# c64-magic-desk-cartridge-smd-256kb.net
KiCad netlist of a schematic drawn in EAGLE
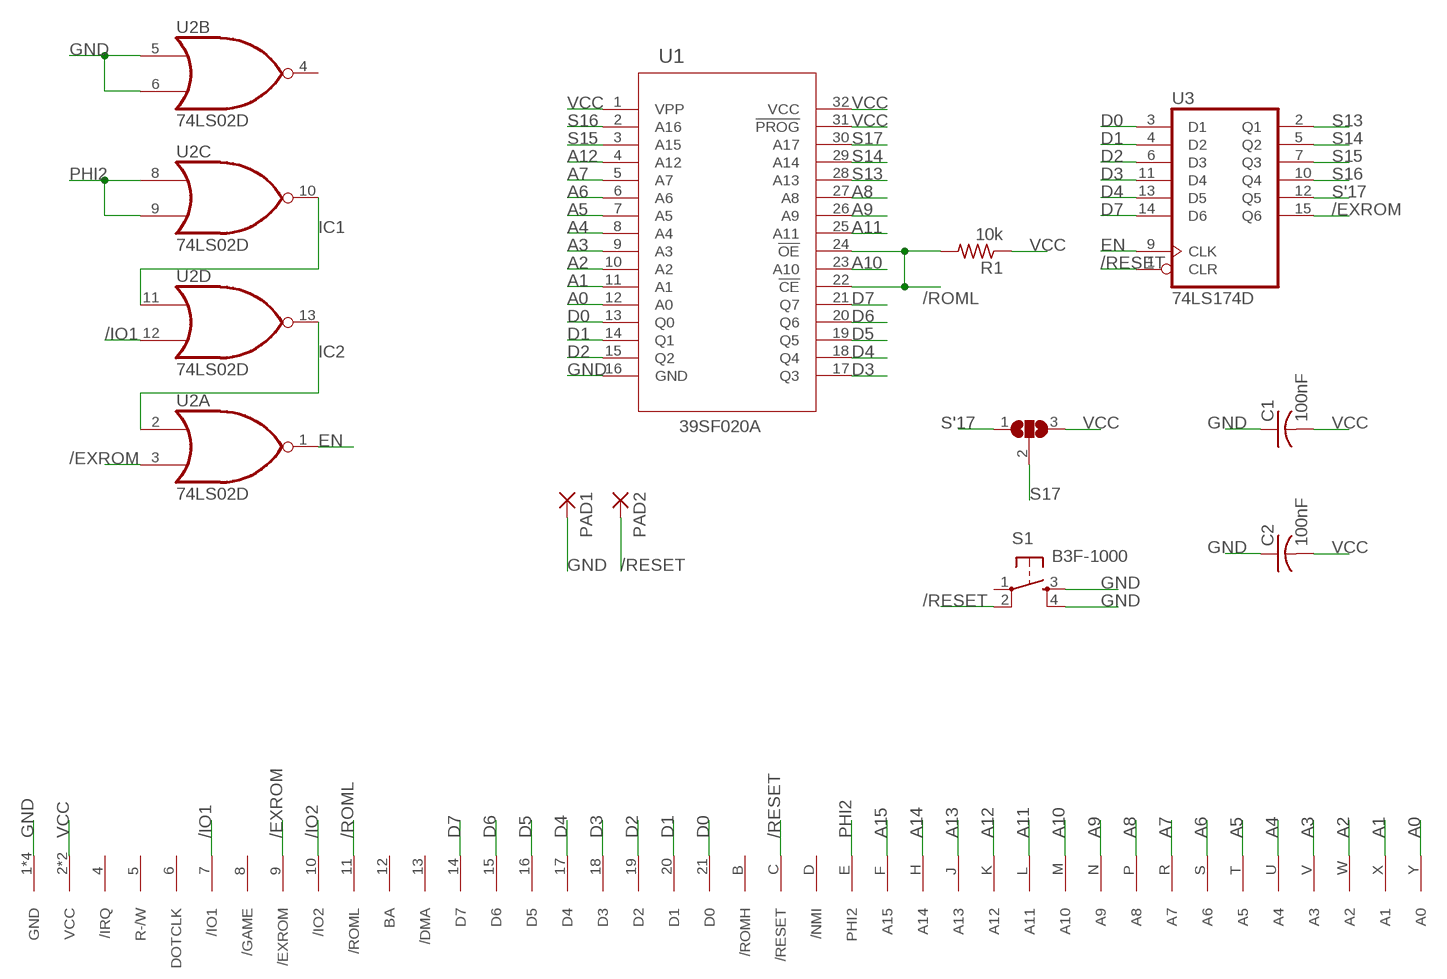
[diagram p0: schematic, sheet 1]

(export (version "E")
  (design (tool "Eeschema 10.0.6"))
  (components
    (comp (ref "C1")
      (value "100nF")
      (footprint "eagle-import:C0805K")
      (libsource (lib "eagle-import") (part "C-USC0805K"))
    )
    (comp (ref "C2")
      (value "100nF")
      (footprint "eagle-import:C0805K")
      (libsource (lib "eagle-import") (part "C-USC0805K"))
    )
    (comp (ref "PAD1")
      (value "SMD2.54-5.08")
      (footprint "eagle-import:SMD2,54-5,08")
      (libsource (lib "eagle-import") (part "SMD2.54-5.08"))
    )
    (comp (ref "PAD2")
      (value "SMD2.54-5.08")
      (footprint "eagle-import:SMD2,54-5,08")
      (libsource (lib "eagle-import") (part "SMD2.54-5.08"))
    )
    (comp (ref "R1")
      (value "10k")
      (footprint "eagle-import:R0805")
      (libsource (lib "eagle-import") (part "R-US_R0805"))
    )
    (comp (ref "S1")
      (value "B3F-1000")
      (footprint "eagle-import:B3F-10XX")
      (libsource (lib "eagle-import") (part "B3F-1000"))
    )
    (comp (ref "SJ1")
      (value "SJ2W")
      (footprint "eagle-import:SJ_2")
      (libsource (lib "eagle-import") (part "SJ2W"))
    )
    (comp (ref "U$1")
      (value "C64-EXPANSION-PORT")
      (footprint "eagle-import:EXPANSION_PORT")
      (libsource (lib "eagle-import") (part "C64-EXPANSION-PORT"))
    )
    (comp (ref "U1")
      (value "M27C2001DIP32-LOWERED")
      (footprint "eagle-import:DIP32")
      (libsource (lib "eagle-import") (part "M27C2001DIP32-LOWERED"))
    )
    (comp (ref "U2")
      (value "74LS02D")
      (footprint "eagle-import:SO14")
      (libsource (lib "eagle-import") (part "7402DLS"))
    )
    (comp (ref "U3")
      (value "74LS174D")
      (footprint "eagle-import:SO16")
      (libsource (lib "eagle-import") (part "74174DLS"))
    )
  )
  (nets
    (net (code "1") (name "/A0") (class "Default")
      (node (ref "U$1") (pin "Y") (pinfunction "A0_Y") (pintype "bidirectional"))
      (node (ref "U1") (pin "12") (pinfunction "A0_12") (pintype "input"))
    )
    (net (code "2") (name "/A1") (class "Default")
      (node (ref "U$1") (pin "X") (pinfunction "A1_X") (pintype "bidirectional"))
      (node (ref "U1") (pin "11") (pinfunction "A1_11") (pintype "input"))
    )
    (net (code "3") (name "/A2") (class "Default")
      (node (ref "U$1") (pin "W") (pinfunction "A2_W") (pintype "bidirectional"))
      (node (ref "U1") (pin "10") (pinfunction "A2_10") (pintype "input"))
    )
    (net (code "4") (name "/A3") (class "Default")
      (node (ref "U$1") (pin "V") (pinfunction "A3_V") (pintype "bidirectional"))
      (node (ref "U1") (pin "9") (pinfunction "A3_9") (pintype "input"))
    )
    (net (code "5") (name "/A4") (class "Default")
      (node (ref "U$1") (pin "U") (pinfunction "A4_U") (pintype "bidirectional"))
      (node (ref "U1") (pin "8") (pinfunction "A4_8") (pintype "input"))
    )
    (net (code "6") (name "/A5") (class "Default")
      (node (ref "U$1") (pin "T") (pinfunction "A5_T") (pintype "bidirectional"))
      (node (ref "U1") (pin "7") (pinfunction "A5_7") (pintype "input"))
    )
    (net (code "7") (name "/A6") (class "Default")
      (node (ref "U$1") (pin "S") (pinfunction "A6_S") (pintype "bidirectional"))
      (node (ref "U1") (pin "6") (pinfunction "A6_6") (pintype "input"))
    )
    (net (code "8") (name "/A7") (class "Default")
      (node (ref "U$1") (pin "R") (pinfunction "A7_R") (pintype "bidirectional"))
      (node (ref "U1") (pin "5") (pinfunction "A7_5") (pintype "input"))
    )
    (net (code "9") (name "/A8") (class "Default")
      (node (ref "U$1") (pin "P") (pinfunction "A8_P") (pintype "bidirectional"))
      (node (ref "U1") (pin "27") (pinfunction "A8_27") (pintype "input"))
    )
    (net (code "10") (name "/A9") (class "Default")
      (node (ref "U$1") (pin "N") (pinfunction "A9_N") (pintype "bidirectional"))
      (node (ref "U1") (pin "26") (pinfunction "A9_26") (pintype "input"))
    )
    (net (code "11") (name "/A10") (class "Default")
      (node (ref "U$1") (pin "M") (pinfunction "A10_M") (pintype "bidirectional"))
      (node (ref "U1") (pin "23") (pinfunction "A10_23") (pintype "input"))
    )
    (net (code "12") (name "/A11") (class "Default")
      (node (ref "U$1") (pin "L") (pinfunction "A11_L") (pintype "bidirectional"))
      (node (ref "U1") (pin "25") (pinfunction "A11_25") (pintype "input"))
    )
    (net (code "13") (name "/A12") (class "Default")
      (node (ref "U$1") (pin "K") (pinfunction "A12_K") (pintype "bidirectional"))
      (node (ref "U1") (pin "4") (pinfunction "A12_4") (pintype "input"))
    )
    (net (code "14") (name "/A13") (class "Default")
      (node (ref "U$1") (pin "J") (pinfunction "A13_J") (pintype "bidirectional"))
    )
    (net (code "15") (name "/A14") (class "Default")
      (node (ref "U$1") (pin "H") (pinfunction "A14_H") (pintype "bidirectional"))
    )
    (net (code "16") (name "/A15") (class "Default")
      (node (ref "U$1") (pin "F") (pinfunction "A15_F") (pintype "bidirectional"))
    )
    (net (code "17") (name "/D0") (class "Default")
      (node (ref "U$1") (pin "21") (pinfunction "D0_21") (pintype "bidirectional"))
      (node (ref "U1") (pin "13") (pinfunction "Q0_13") (pintype "bidirectional"))
      (node (ref "U3") (pin "3") (pinfunction "D1_3") (pintype "input"))
    )
    (net (code "18") (name "/D1") (class "Default")
      (node (ref "U$1") (pin "20") (pinfunction "D1_20") (pintype "bidirectional"))
      (node (ref "U1") (pin "14") (pinfunction "Q1_14") (pintype "bidirectional"))
      (node (ref "U3") (pin "4") (pinfunction "D2_4") (pintype "input"))
    )
    (net (code "19") (name "/D2") (class "Default")
      (node (ref "U$1") (pin "19") (pinfunction "D2_19") (pintype "bidirectional"))
      (node (ref "U1") (pin "15") (pinfunction "Q2_15") (pintype "bidirectional"))
      (node (ref "U3") (pin "6") (pinfunction "D3_6") (pintype "input"))
    )
    (net (code "20") (name "/D3") (class "Default")
      (node (ref "U$1") (pin "18") (pinfunction "D3_18") (pintype "bidirectional"))
      (node (ref "U1") (pin "17") (pinfunction "Q3_17") (pintype "bidirectional"))
      (node (ref "U3") (pin "11") (pinfunction "D4_11") (pintype "input"))
    )
    (net (code "21") (name "/D4") (class "Default")
      (node (ref "U$1") (pin "17") (pinfunction "D4_17") (pintype "bidirectional"))
      (node (ref "U1") (pin "18") (pinfunction "Q4_18") (pintype "bidirectional"))
      (node (ref "U3") (pin "13") (pinfunction "D5_13") (pintype "input"))
    )
    (net (code "22") (name "/D5") (class "Default")
      (node (ref "U$1") (pin "16") (pinfunction "D5_16") (pintype "bidirectional"))
      (node (ref "U1") (pin "19") (pinfunction "Q5_19") (pintype "bidirectional"))
    )
    (net (code "23") (name "/D6") (class "Default")
      (node (ref "U$1") (pin "15") (pinfunction "D6_15") (pintype "bidirectional"))
      (node (ref "U1") (pin "20") (pinfunction "Q6_20") (pintype "bidirectional"))
    )
    (net (code "24") (name "/D7") (class "Default")
      (node (ref "U$1") (pin "14") (pinfunction "D7_14") (pintype "bidirectional"))
      (node (ref "U1") (pin "21") (pinfunction "Q7_21") (pintype "bidirectional"))
      (node (ref "U3") (pin "14") (pinfunction "D6_14") (pintype "input"))
    )
    (net (code "25") (name "/EN") (class "Default")
      (node (ref "U2") (pin "1") (pinfunction "O_1") (pintype "output"))
      (node (ref "U3") (pin "9") (pinfunction "CLK_9") (pintype "input"))
    )
    (net (code "26") (name "/GND") (class "Default")
      (node (ref "C1") (pin "1") (pinfunction "1_1") (pintype "passive"))
      (node (ref "C2") (pin "1") (pinfunction "1_1") (pintype "passive"))
      (node (ref "PAD1") (pin "P$1") (pinfunction "P_P$1") (pintype "passive"))
      (node (ref "S1") (pin "3") (pinfunction "S_3") (pintype "passive"))
      (node (ref "S1") (pin "4") (pinfunction "S1_4") (pintype "passive"))
      (node (ref "U$1") (pin "1") (pinfunction "GND_1") (pintype "bidirectional"))
      (node (ref "U$1") (pin "22") (pinfunction "GND_22") (pintype "bidirectional"))
      (node (ref "U$1") (pin "A") (pinfunction "GND_A") (pintype "bidirectional"))
      (node (ref "U$1") (pin "Z") (pinfunction "GND_Z") (pintype "bidirectional"))
      (node (ref "U1") (pin "16") (pinfunction "GND_16") (pintype "power_in"))
      (node (ref "U2") (pin "5") (pinfunction "I0_5") (pintype "input"))
      (node (ref "U2") (pin "6") (pinfunction "I1_6") (pintype "input"))
    )
    (net (code "27") (name "/IC1") (class "Default")
      (node (ref "U2") (pin "10") (pinfunction "O_10") (pintype "output"))
      (node (ref "U2") (pin "11") (pinfunction "I0_11") (pintype "input"))
    )
    (net (code "28") (name "/IC2") (class "Default")
      (node (ref "U2") (pin "13") (pinfunction "O_13") (pintype "output"))
      (node (ref "U2") (pin "2") (pinfunction "I0_2") (pintype "input"))
    )
    (net (code "29") (name "/PHI2") (class "Default")
      (node (ref "U$1") (pin "E") (pinfunction "PHI2_E") (pintype "bidirectional"))
      (node (ref "U2") (pin "8") (pinfunction "I0_8") (pintype "input"))
      (node (ref "U2") (pin "9") (pinfunction "I1_9") (pintype "input"))
    )
    (net (code "30") (name "/S'17") (class "Default")
      (node (ref "SJ1") (pin "1") (pinfunction "1_1") (pintype "passive"))
      (node (ref "U3") (pin "12") (pinfunction "Q5_12") (pintype "output"))
    )
    (net (code "31") (name "/S13") (class "Default")
      (node (ref "U1") (pin "28") (pinfunction "A13_28") (pintype "input"))
      (node (ref "U3") (pin "2") (pinfunction "Q1_2") (pintype "output"))
    )
    (net (code "32") (name "/S14") (class "Default")
      (node (ref "U1") (pin "29") (pinfunction "A14_29") (pintype "input"))
      (node (ref "U3") (pin "5") (pinfunction "Q2_5") (pintype "output"))
    )
    (net (code "33") (name "/S15") (class "Default")
      (node (ref "U1") (pin "3") (pinfunction "A15_3") (pintype "input"))
      (node (ref "U3") (pin "7") (pinfunction "Q3_7") (pintype "output"))
    )
    (net (code "34") (name "/S16") (class "Default")
      (node (ref "U1") (pin "2") (pinfunction "A16_2") (pintype "input"))
      (node (ref "U3") (pin "10") (pinfunction "Q4_10") (pintype "output"))
    )
    (net (code "35") (name "/S17") (class "Default")
      (node (ref "SJ1") (pin "2") (pinfunction "2_2") (pintype "passive"))
      (node (ref "U1") (pin "30") (pinfunction "A17_30") (pintype "input"))
    )
    (net (code "36") (name "/VCC") (class "Default")
      (node (ref "C1") (pin "2") (pinfunction "2_2") (pintype "passive"))
      (node (ref "C2") (pin "2") (pinfunction "2_2") (pintype "passive"))
      (node (ref "R1") (pin "1") (pinfunction "1_1") (pintype "passive"))
      (node (ref "SJ1") (pin "3") (pinfunction "3_3") (pintype "passive"))
      (node (ref "U$1") (pin "2") (pinfunction "VCC_2") (pintype "bidirectional"))
      (node (ref "U$1") (pin "3") (pinfunction "VCC_3") (pintype "bidirectional"))
      (node (ref "U1") (pin "1") (pinfunction "VPP_1") (pintype "power_in"))
      (node (ref "U1") (pin "31") (pinfunction "~{PROG}_31") (pintype "input"))
      (node (ref "U1") (pin "32") (pinfunction "VCC_32") (pintype "power_in"))
    )
    (net (code "37") (name "/{slash}EXROM") (class "Default")
      (node (ref "U$1") (pin "9") (pinfunction "/EXROM_9") (pintype "bidirectional"))
      (node (ref "U2") (pin "3") (pinfunction "I1_3") (pintype "input"))
      (node (ref "U3") (pin "15") (pinfunction "Q6_15") (pintype "output"))
    )
    (net (code "38") (name "/{slash}IO1") (class "Default")
      (node (ref "U$1") (pin "7") (pinfunction "/IO1_7") (pintype "bidirectional"))
      (node (ref "U2") (pin "12") (pinfunction "I1_12") (pintype "input"))
    )
    (net (code "39") (name "/{slash}IO2") (class "Default")
      (node (ref "U$1") (pin "10") (pinfunction "/IO2_10") (pintype "bidirectional"))
    )
    (net (code "40") (name "/{slash}RESET") (class "Default")
      (node (ref "PAD2") (pin "P$1") (pinfunction "P_P$1") (pintype "passive"))
      (node (ref "S1") (pin "2") (pinfunction "P1_2") (pintype "passive"))
      (node (ref "U$1") (pin "C") (pinfunction "/RESET_C") (pintype "bidirectional"))
      (node (ref "U3") (pin "1") (pinfunction "CLR_1") (pintype "input"))
    )
    (net (code "41") (name "/{slash}ROML") (class "Default")
      (node (ref "R1") (pin "2") (pinfunction "2_2") (pintype "passive"))
      (node (ref "U$1") (pin "11") (pinfunction "/ROML_11") (pintype "bidirectional"))
      (node (ref "U1") (pin "22") (pinfunction "~{CE}_22") (pintype "input"))
      (node (ref "U1") (pin "24") (pinfunction "~{OE}_24") (pintype "input"))
    )
    (net (code "42") (name "unconnected-(S1-P-Pad1)") (class "Default")
      (node (ref "S1") (pin "1") (pinfunction "P_1") (pintype "passive"))
    )
    (net (code "43") (name "unconnected-(U$1-BA-Pad12)") (class "Default")
      (node (ref "U$1") (pin "12") (pinfunction "BA_12") (pintype "bidirectional"))
    )
    (net (code "44") (name "unconnected-(U$1-DOTCLK-Pad6)") (class "Default")
      (node (ref "U$1") (pin "6") (pinfunction "DOTCLK_6") (pintype "bidirectional"))
    )
    (net (code "45") (name "unconnected-(U$1-R-{slash}W-Pad5)") (class "Default")
      (node (ref "U$1") (pin "5") (pinfunction "R-/W_5") (pintype "bidirectional"))
    )
    (net (code "46") (name "unconnected-(U$1-{slash}DMA-Pad13)") (class "Default")
      (node (ref "U$1") (pin "13") (pinfunction "/DMA_13") (pintype "bidirectional"))
    )
    (net (code "47") (name "unconnected-(U$1-{slash}GAME-Pad8)") (class "Default")
      (node (ref "U$1") (pin "8") (pinfunction "/GAME_8") (pintype "bidirectional"))
    )
    (net (code "48") (name "unconnected-(U$1-{slash}IRQ-Pad4)") (class "Default")
      (node (ref "U$1") (pin "4") (pinfunction "/IRQ_4") (pintype "bidirectional"))
    )
    (net (code "49") (name "unconnected-(U$1-{slash}NMI-PadD)") (class "Default")
      (node (ref "U$1") (pin "D") (pinfunction "/NMI_D") (pintype "bidirectional"))
    )
    (net (code "50") (name "unconnected-(U$1-{slash}ROMH-PadB)") (class "Default")
      (node (ref "U$1") (pin "B") (pinfunction "/ROMH_B") (pintype "bidirectional"))
    )
    (net (code "51") (name "unconnected-(U2B-O-Pad4)") (class "Default")
      (node (ref "U2") (pin "4") (pinfunction "O_4") (pintype "output"))
    )
  )
)
